# ControlBoard.net
KiCad netlist of a schematic drawn in Altium Designer
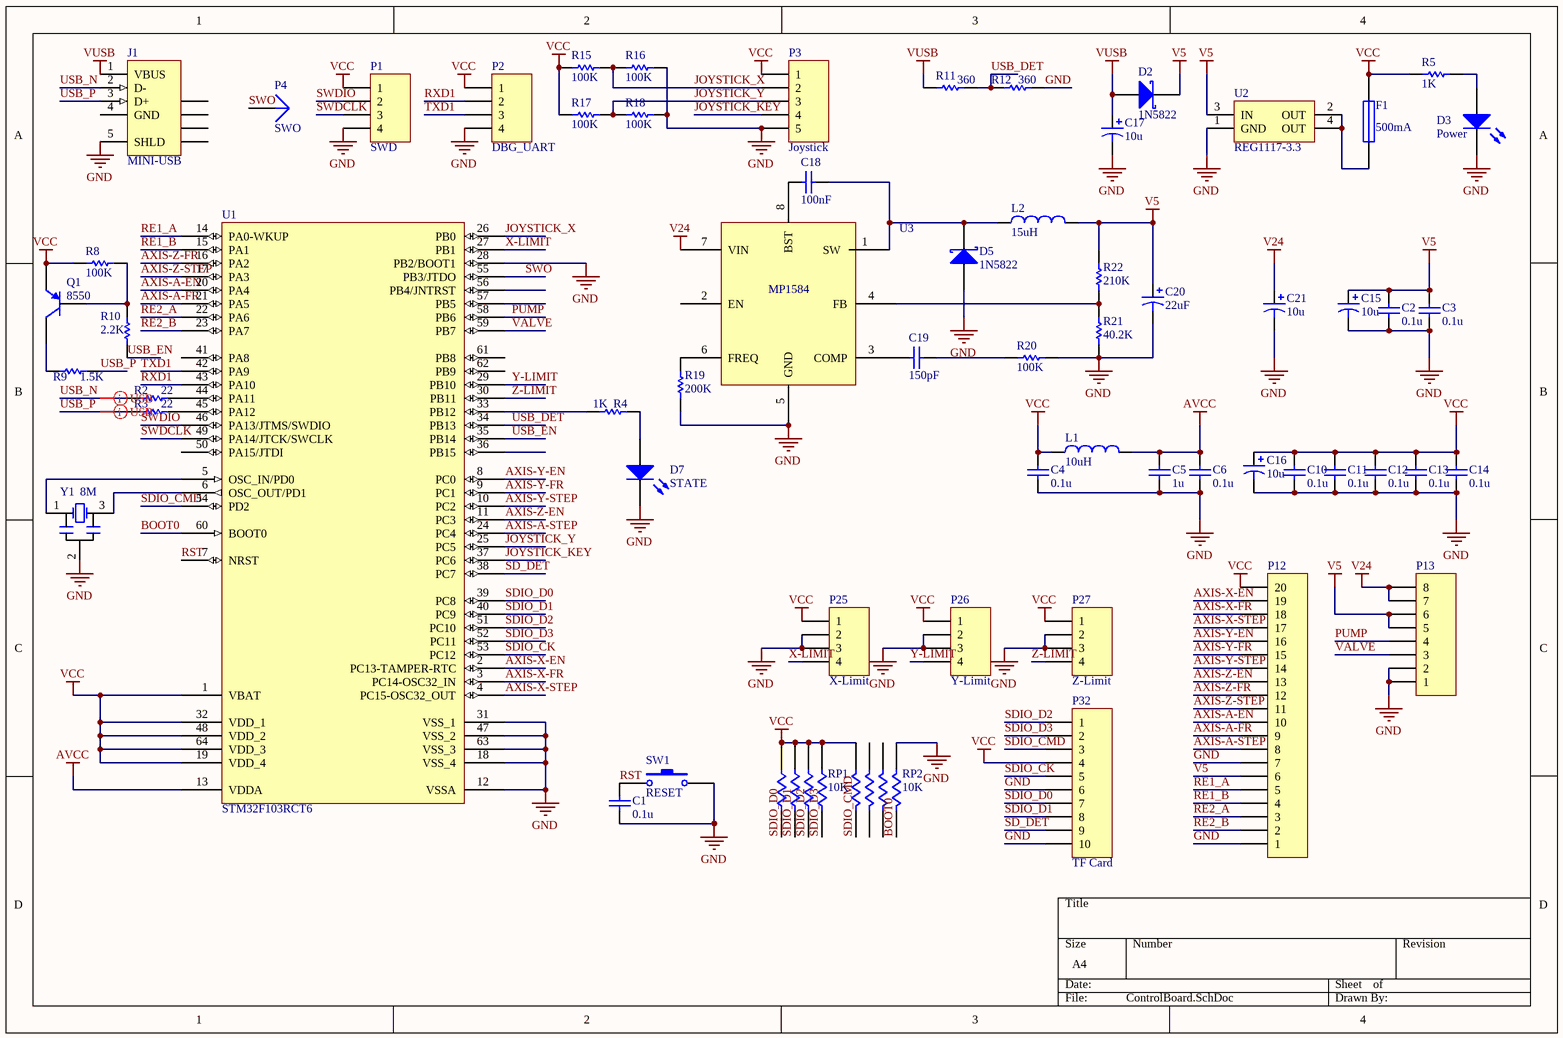
[diagram p0: ControlBoard.SchDoc]

(export (version "E")
  (design (tool "Eeschema 10.0.6"))
  (components
    (comp (ref "C1")
      (value "0.1u")
      (footprint "C-1608[0603]")
      (description "Capacitor (Semiconductor SIM Model)")
      (fields (field (name "Comment") "Cap Semi") (field (name "PUBLISHER") "Altium Limited"))
      (libsource (lib "Miscellaneous Devices") (part "Cap Semi"))
    )
    (comp (ref "C2")
      (value "0.1u")
      (footprint "C-1608[0603]")
      (description "Capacitor (Semiconductor SIM Model)")
      (fields (field (name "Comment") "Cap Semi") (field (name "PUBLISHER") "Altium Limited"))
      (libsource (lib "Miscellaneous Devices") (part "Cap Semi"))
    )
    (comp (ref "C3")
      (value "0.1u")
      (footprint "C-1608[0603]")
      (description "Capacitor (Semiconductor SIM Model)")
      (fields (field (name "Comment") "Cap Semi") (field (name "PUBLISHER") "Altium Limited"))
      (libsource (lib "Miscellaneous Devices") (part "Cap Semi"))
    )
    (comp (ref "C4")
      (value "0.1u")
      (footprint "C-1608[0603]")
      (description "Capacitor (Semiconductor SIM Model)")
      (fields (field (name "Comment") "Cap Semi") (field (name "PUBLISHER") "Altium Limited"))
      (libsource (lib "Miscellaneous Devices") (part "Cap Semi"))
    )
    (comp (ref "C5")
      (value "1u")
      (footprint "C-1608[0603]")
      (description "Capacitor (Semiconductor SIM Model)")
      (fields (field (name "Comment") "Cap Semi") (field (name "PUBLISHER") "Altium Limited"))
      (libsource (lib "Miscellaneous Devices") (part "Cap Semi"))
    )
    (comp (ref "C6")
      (value "0.1u")
      (footprint "C-1608[0603]")
      (description "Capacitor (Semiconductor SIM Model)")
      (fields (field (name "Comment") "Cap Semi") (field (name "PUBLISHER") "Altium Limited"))
      (libsource (lib "Miscellaneous Devices") (part "Cap Semi"))
    )
    (comp (ref "C10")
      (value "0.1u")
      (footprint "C-1608[0603]")
      (description "Capacitor (Semiconductor SIM Model)")
      (fields (field (name "Comment") "Cap Semi") (field (name "PUBLISHER") "Altium Limited"))
      (libsource (lib "Miscellaneous Devices") (part "Cap Semi"))
    )
    (comp (ref "C11")
      (value "0.1u")
      (footprint "C-1608[0603]")
      (description "Capacitor (Semiconductor SIM Model)")
      (fields (field (name "Comment") "Cap Semi") (field (name "PUBLISHER") "Altium Limited"))
      (libsource (lib "Miscellaneous Devices") (part "Cap Semi"))
    )
    (comp (ref "C12")
      (value "0.1u")
      (footprint "C-1608[0603]")
      (description "Capacitor (Semiconductor SIM Model)")
      (fields (field (name "Comment") "Cap Semi") (field (name "PUBLISHER") "Altium Limited"))
      (libsource (lib "Miscellaneous Devices") (part "Cap Semi"))
    )
    (comp (ref "C13")
      (value "0.1u")
      (footprint "C-1608[0603]")
      (description "Capacitor (Semiconductor SIM Model)")
      (fields (field (name "Comment") "Cap Semi") (field (name "PUBLISHER") "Altium Limited"))
      (libsource (lib "Miscellaneous Devices") (part "Cap Semi"))
    )
    (comp (ref "C14")
      (value "0.1u")
      (footprint "C-1608[0603]")
      (description "Capacitor (Semiconductor SIM Model)")
      (fields (field (name "Comment") "Cap Semi") (field (name "PUBLISHER") "Altium Limited"))
      (libsource (lib "Miscellaneous Devices") (part "Cap Semi"))
    )
    (comp (ref "C15")
      (value "10u")
      (footprint "C-2012[0805]")
      (description "Polarized Capacitor (Surface Mount)")
      (fields (field (name "Comment") "Cap Pol3") (field (name "PUBLISHER") "Altium Limited"))
      (libsource (lib "Miscellaneous Devices") (part "Cap Pol3"))
    )
    (comp (ref "C16")
      (value "10u")
      (footprint "C-2012[0805]")
      (description "Polarized Capacitor (Surface Mount)")
      (fields (field (name "Comment") "Cap Pol3") (field (name "PUBLISHER") "Altium Limited"))
      (libsource (lib "Miscellaneous Devices") (part "Cap Pol3"))
    )
    (comp (ref "C17")
      (value "10u")
      (footprint "C-2012[0805]")
      (description "Polarized Capacitor (Surface Mount)")
      (fields (field (name "Comment") "Cap Pol3") (field (name "PUBLISHER") "Altium Limited"))
      (libsource (lib "Miscellaneous Devices") (part "Cap Pol3"))
    )
    (comp (ref "C18")
      (value "100nF")
      (footprint "C-1608[0603]")
      (description "Capacitor (Semiconductor SIM Model)")
      (fields (field (name "Comment") "Cap Semi") (field (name "PUBLISHER") "Altium Limited"))
      (libsource (lib "Miscellaneous Devices") (part "Cap Semi"))
    )
    (comp (ref "C19")
      (value "150pF")
      (footprint "C-1608[0603]")
      (description "Capacitor (Semiconductor SIM Model)")
      (fields (field (name "Comment") "Cap Semi") (field (name "PUBLISHER") "Altium Limited"))
      (libsource (lib "Miscellaneous Devices") (part "Cap Semi"))
    )
    (comp (ref "C20")
      (value "22uF")
      (footprint "C1206")
      (description "Polarized Capacitor (Surface Mount)")
      (fields (field (name "Comment") "Cap Pol3") (field (name "PUBLISHER") "Altium Limited"))
      (libsource (lib "Miscellaneous Devices") (part "Cap Pol3"))
    )
    (comp (ref "C21")
      (value "10u")
      (footprint "C1206")
      (description "Polarized Capacitor (Surface Mount)")
      (fields (field (name "Comment") "Cap Pol3") (field (name "PUBLISHER") "Altium Limited"))
      (libsource (lib "Miscellaneous Devices") (part "Cap Pol3"))
    )
    (comp (ref "D2")
      (value "1N5822")
      (footprint "DO-214AC")
      (description "Schottky Diode")
      (fields (field (name "PUBLISHER") "Altium Limited"))
      (libsource (lib "Miscellaneous Devices") (part "D Schottky"))
    )
    (comp (ref "D3")
      (value "Power")
      (footprint "LED-0805")
      (description "Typical RED, GREEN, YELLOW, AMBER GaAs LED")
      (fields (field (name "PUBLISHER") "Altium Limited"))
      (libsource (lib "Miscellaneous Devices") (part "LED2"))
    )
    (comp (ref "D5")
      (value "1N5822")
      (footprint "DO-214AC")
      (description "Schottky Diode")
      (fields (field (name "PUBLISHER") "Altium Limited"))
      (libsource (lib "Miscellaneous Devices") (part "D Schottky"))
    )
    (comp (ref "D7")
      (value "STATE")
      (footprint "LED-0805")
      (description "Typical RED, GREEN, YELLOW, AMBER GaAs LED")
      (fields (field (name "PUBLISHER") "Altium Limited"))
      (libsource (lib "Miscellaneous Devices") (part "LED2"))
    )
    (comp (ref "F1")
      (value "500mA")
      (footprint "2012[0805]")
      (description "Fuse")
      (fields (field (name "PUBLISHER") "Altium Limited"))
      (libsource (lib "Miscellaneous Devices") (part "Fuse 1"))
    )
    (comp (ref "J1")
      (value "MINI-USB")
      (footprint "Mini USB 3D")
      (description "USB 2.0, Right Angle, SMT, A Type, Receptacle, 5 Position, Black")
      (fields (field (name "PUBLISHER") "Altium Limited"))
      (libsource (lib "AMP Serial Bus USB") (part "440478-1"))
    )
    (comp (ref "L1")
      (value "10uH")
      (footprint "L0603")
      (description "Inductor")
      (fields (field (name "PUBLISHER") "Altium Limited"))
      (libsource (lib "Miscellaneous Devices") (part "Inductor"))
    )
    (comp (ref "L2")
      (value "15uH")
      (footprint "GDRH104R")
      (description "Inductor")
      (fields (field (name "PUBLISHER") "Altium Limited"))
      (libsource (lib "Miscellaneous Devices") (part "Inductor"))
    )
    (comp (ref "P1")
      (value "SWD")
      (footprint "HDR1X4")
      (description "Header, 4-Pin")
      (fields (field (name "PUBLISHER") "Altium Limited"))
      (libsource (lib "Miscellaneous Connectors") (part "Header 4"))
    )
    (comp (ref "P2")
      (value "DBG_UART")
      (footprint "HDR1X4")
      (description "Header, 4-Pin")
      (fields (field (name "PUBLISHER") "Altium Limited"))
      (libsource (lib "Miscellaneous Connectors") (part "Header 4"))
    )
    (comp (ref "P3")
      (value "Joystick")
      (footprint "HDR1X5")
      (description "Header, 5-Pin")
      (fields (field (name "PUBLISHER") "Altium Limited"))
      (libsource (lib "Miscellaneous Connectors") (part "Header 5"))
    )
    (comp (ref "P4")
      (value "SWO")
      (footprint "HDR1X1")
      (description "Plug")
      (fields (field (name "PUBLISHER") "Altium Limited"))
      (libsource (lib "Miscellaneous Connectors") (part "Plug"))
    )
    (comp (ref "P12")
      (value "Header 20")
      (footprint "HDR1X20-3D")
      (description "Header, 20-Pin")
      (fields (field (name "PUBLISHER") "Altium Limited"))
      (libsource (lib "Miscellaneous Connectors") (part "Header 20"))
    )
    (comp (ref "P13")
      (value "Header 8")
      (footprint "HDR1X8-3D")
      (description "Header, 8-Pin")
      (fields (field (name "PUBLISHER") "Altium Limited"))
      (libsource (lib "Miscellaneous Connectors") (part "Header 8"))
    )
    (comp (ref "P25")
      (value "X-Limit")
      (footprint "HDR1X4")
      (description "Header, 4-Pin")
      (fields (field (name "PUBLISHER") "Altium Limited"))
      (libsource (lib "Miscellaneous Connectors") (part "Header 4"))
    )
    (comp (ref "P26")
      (value "Y-Limit")
      (footprint "HDR1X4")
      (description "Header, 4-Pin")
      (fields (field (name "PUBLISHER") "Altium Limited"))
      (libsource (lib "Miscellaneous Connectors") (part "Header 4"))
    )
    (comp (ref "P27")
      (value "Z-Limit")
      (footprint "HDR1X4")
      (description "Header, 4-Pin")
      (fields (field (name "PUBLISHER") "Altium Limited"))
      (libsource (lib "Miscellaneous Connectors") (part "Header 4"))
    )
    (comp (ref "P32")
      (value "TF Card")
      (footprint "MicroSD auto")
      (description "Header, 10-Pin")
      (fields (field (name "PUBLISHER") "Altium Limited"))
      (libsource (lib "Miscellaneous Connectors") (part "Header 10"))
    )
    (comp (ref "Q1")
      (value "8550")
      (footprint "SOT23B")
      (description "PNP Bipolar Transistor")
      (fields (field (name "PUBLISHER") "Altium Limited"))
      (libsource (lib "Miscellaneous Devices") (part "PNP"))
    )
    (comp (ref "R2")
      (value "22")
      (footprint "R-1608[0603]")
      (description "Semiconductor Resistor")
      (fields (field (name "Comment") "Res Semi") (field (name "PUBLISHER") "Altium Limited"))
      (libsource (lib "Miscellaneous Devices") (part "Res Semi"))
    )
    (comp (ref "R3")
      (value "22")
      (footprint "R-1608[0603]")
      (description "Semiconductor Resistor")
      (fields (field (name "Comment") "Res Semi") (field (name "PUBLISHER") "Altium Limited"))
      (libsource (lib "Miscellaneous Devices") (part "Res Semi"))
    )
    (comp (ref "R4")
      (value "1K")
      (footprint "R-1608[0603]")
      (description "Semiconductor Resistor")
      (fields (field (name "Comment") "Res Semi") (field (name "PUBLISHER") "Altium Limited"))
      (libsource (lib "Miscellaneous Devices") (part "Res Semi"))
    )
    (comp (ref "R5")
      (value "1K")
      (footprint "R-1608[0603]")
      (description "Semiconductor Resistor")
      (fields (field (name "Comment") "Res Semi") (field (name "PUBLISHER") "Altium Limited"))
      (libsource (lib "Miscellaneous Devices") (part "Res Semi"))
    )
    (comp (ref "R8")
      (value "100K")
      (footprint "R-1608[0603]")
      (description "Semiconductor Resistor")
      (fields (field (name "Comment") "Res Semi") (field (name "PUBLISHER") "Altium Limited"))
      (libsource (lib "Miscellaneous Devices") (part "Res Semi"))
    )
    (comp (ref "R9")
      (value "1.5K")
      (footprint "R-1608[0603]")
      (description "Semiconductor Resistor")
      (fields (field (name "Comment") "Res Semi") (field (name "PUBLISHER") "Altium Limited"))
      (libsource (lib "Miscellaneous Devices") (part "Res Semi"))
    )
    (comp (ref "R10")
      (value "2.2K")
      (footprint "R-1608[0603]")
      (description "Semiconductor Resistor")
      (fields (field (name "Comment") "Res Semi") (field (name "PUBLISHER") "Altium Limited"))
      (libsource (lib "Miscellaneous Devices") (part "Res Semi"))
    )
    (comp (ref "R11")
      (value "360")
      (footprint "R-1608[0603]")
      (description "Semiconductor Resistor")
      (fields (field (name "Comment") "Res Semi") (field (name "PUBLISHER") "Altium Limited"))
      (libsource (lib "Miscellaneous Devices") (part "Res Semi"))
    )
    (comp (ref "R12")
      (value "360")
      (footprint "R-1608[0603]")
      (description "Semiconductor Resistor")
      (fields (field (name "Comment") "Res Semi") (field (name "PUBLISHER") "Altium Limited"))
      (libsource (lib "Miscellaneous Devices") (part "Res Semi"))
    )
    (comp (ref "R15")
      (value "100K")
      (footprint "R-1608[0603]")
      (description "Semiconductor Resistor")
      (fields (field (name "Comment") "Res Semi") (field (name "PUBLISHER") "Altium Limited"))
      (libsource (lib "Miscellaneous Devices") (part "Res Semi"))
    )
    (comp (ref "R16")
      (value "100K")
      (footprint "R-1608[0603]")
      (description "Semiconductor Resistor")
      (fields (field (name "Comment") "Res Semi") (field (name "PUBLISHER") "Altium Limited"))
      (libsource (lib "Miscellaneous Devices") (part "Res Semi"))
    )
    (comp (ref "R17")
      (value "100K")
      (footprint "R-1608[0603]")
      (description "Semiconductor Resistor")
      (fields (field (name "Comment") "Res Semi") (field (name "PUBLISHER") "Altium Limited"))
      (libsource (lib "Miscellaneous Devices") (part "Res Semi"))
    )
    (comp (ref "R18")
      (value "100K")
      (footprint "R-1608[0603]")
      (description "Semiconductor Resistor")
      (fields (field (name "Comment") "Res Semi") (field (name "PUBLISHER") "Altium Limited"))
      (libsource (lib "Miscellaneous Devices") (part "Res Semi"))
    )
    (comp (ref "R19")
      (value "200K")
      (footprint "R-1608[0603]")
      (description "Semiconductor Resistor")
      (fields (field (name "Comment") "Res Semi") (field (name "PUBLISHER") "Altium Limited"))
      (libsource (lib "Miscellaneous Devices") (part "Res Semi"))
    )
    (comp (ref "R20")
      (value "100K")
      (footprint "R-1608[0603]")
      (description "Semiconductor Resistor")
      (fields (field (name "Comment") "Res Semi") (field (name "PUBLISHER") "Altium Limited"))
      (libsource (lib "Miscellaneous Devices") (part "Res Semi"))
    )
    (comp (ref "R21")
      (value "40.2K")
      (footprint "R-1608[0603]")
      (description "Semiconductor Resistor")
      (fields (field (name "Comment") "Res Semi") (field (name "PUBLISHER") "Altium Limited"))
      (libsource (lib "Miscellaneous Devices") (part "Res Semi"))
    )
    (comp (ref "R22")
      (value "210K")
      (footprint "R-1608[0603]")
      (description "Semiconductor Resistor")
      (fields (field (name "Comment") "Res Semi") (field (name "PUBLISHER") "Altium Limited"))
      (libsource (lib "Miscellaneous Devices") (part "Res Semi"))
    )
    (comp (ref "RP1") (value "10K") (footprint "R0603x4") (libsource (lib "Schlib1") (part "RPACK4")))
    (comp (ref "RP2") (value "10K") (footprint "R0603x4") (libsource (lib "Schlib1") (part "RPACK4")))
    (comp (ref "SW1")
      (value "RESET")
      (footprint "SW-3D")
      (description "Switch")
      (fields (field (name "PUBLISHER") "Altium Limited"))
      (libsource (lib "Miscellaneous Devices") (part "SW-PB"))
    )
    (comp (ref "U1")
      (value "STM32F103RCT6")
      (footprint "LQFP64_N")
      (description "STM32 ARM-based 32-bit MCU High-density")
      (fields (field (name "PUBLISHER") "Altium Limited"))
      (libsource (lib "ST Microcontroller 32-Bit STM32") (part "STM32F103RBT6"))
    )
    (comp (ref "U2")
      (value "REG1117-3.3")
      (footprint "SOT223-3D")
      (description "800mA and 1A Low Dropout Positive Regulator 2.85V, 3.3V, 5V, and Adjustable")
      (fields (field (name "PUBLISHER") "Altium Limited"))
      (libsource (lib "BB Power Mgt Voltage Regulator") (part "REG1117-3.3"))
    )
    (comp (ref "U3") (value "MP1584") (footprint "MP1584") (libsource (lib "Schlib1") (part "MP1584")))
    (comp (ref "Y1")
      (value "8M")
      (footprint "Crystal_C")
      (description "Crystal Oscillator")
      (fields (field (name "PUBLISHER") "Altium Limited"))
      (libsource (lib "Schlib1") (part "XTAL_C"))
    )
  )
  (nets
    (net (code "1") (name "/AXIS-A-EN") (class "Default")
      (node (ref "P12") (pin "10") (pinfunction "10_10") (pintype "passive"))
      (node (ref "U1") (pin "20") (pinfunction "PA4_20") (pintype "bidirectional"))
    )
    (net (code "2") (name "/AXIS-A-FR") (class "Default")
      (node (ref "P12") (pin "9") (pinfunction "9_9") (pintype "passive"))
      (node (ref "U1") (pin "21") (pinfunction "PA5_21") (pintype "bidirectional"))
    )
    (net (code "3") (name "/AXIS-A-STEP") (class "Default")
      (node (ref "P12") (pin "8") (pinfunction "8_8") (pintype "passive"))
      (node (ref "U1") (pin "24") (pinfunction "PC4_24") (pintype "bidirectional"))
    )
    (net (code "4") (name "/AXIS-X-EN") (class "Default")
      (node (ref "P12") (pin "19") (pinfunction "19_19") (pintype "passive"))
      (node (ref "U1") (pin "2") (pinfunction "PC13-TAMPER-RTC_2") (pintype "bidirectional"))
    )
    (net (code "5") (name "/AXIS-X-FR") (class "Default")
      (node (ref "P12") (pin "18") (pinfunction "18_18") (pintype "passive"))
      (node (ref "U1") (pin "3") (pinfunction "PC14-OSC32_IN_3") (pintype "bidirectional"))
    )
    (net (code "6") (name "/AXIS-X-STEP") (class "Default")
      (node (ref "P12") (pin "17") (pinfunction "17_17") (pintype "passive"))
      (node (ref "U1") (pin "4") (pinfunction "PC15-OSC32_OUT_4") (pintype "bidirectional"))
    )
    (net (code "7") (name "/AXIS-Y-EN") (class "Default")
      (node (ref "P12") (pin "16") (pinfunction "16_16") (pintype "passive"))
      (node (ref "U1") (pin "8") (pinfunction "PC0_8") (pintype "bidirectional"))
    )
    (net (code "8") (name "/AXIS-Y-FR") (class "Default")
      (node (ref "P12") (pin "15") (pinfunction "15_15") (pintype "passive"))
      (node (ref "U1") (pin "9") (pinfunction "PC1_9") (pintype "bidirectional"))
    )
    (net (code "9") (name "/AXIS-Y-STEP") (class "Default")
      (node (ref "P12") (pin "14") (pinfunction "14_14") (pintype "passive"))
      (node (ref "U1") (pin "10") (pinfunction "PC2_10") (pintype "bidirectional"))
    )
    (net (code "10") (name "/AXIS-Z-EN") (class "Default")
      (node (ref "P12") (pin "13") (pinfunction "13_13") (pintype "passive"))
      (node (ref "U1") (pin "11") (pinfunction "PC3_11") (pintype "bidirectional"))
    )
    (net (code "11") (name "/AXIS-Z-FR") (class "Default")
      (node (ref "P12") (pin "12") (pinfunction "12_12") (pintype "passive"))
      (node (ref "U1") (pin "16") (pinfunction "PA2_16") (pintype "bidirectional"))
    )
    (net (code "12") (name "/AXIS-Z-STEP") (class "Default")
      (node (ref "P12") (pin "11") (pinfunction "11_11") (pintype "passive"))
      (node (ref "U1") (pin "17") (pinfunction "PA3_17") (pintype "bidirectional"))
    )
    (net (code "13") (name "/BOOT0") (class "Default")
      (node (ref "RP2") (pin "5") (pinfunction "5_5") (pintype "passive"))
      (node (ref "U1") (pin "60") (pinfunction "BOOT0_60") (pintype "input"))
    )
    (net (code "14") (name "/JOYSTICK_KEY") (class "Default")
      (node (ref "P3") (pin "4") (pinfunction "4_4") (pintype "passive"))
      (node (ref "U1") (pin "37") (pinfunction "PC6_37") (pintype "bidirectional"))
    )
    (net (code "15") (name "/JOYSTICK_X") (class "Default")
      (node (ref "P3") (pin "2") (pinfunction "2_2") (pintype "passive"))
      (node (ref "R15") (pin "1") (pinfunction "1_1") (pintype "passive"))
      (node (ref "R16") (pin "2") (pinfunction "2_2") (pintype "passive"))
      (node (ref "U1") (pin "26") (pinfunction "PB0_26") (pintype "bidirectional"))
    )
    (net (code "16") (name "/JOYSTICK_Y") (class "Default")
      (node (ref "P3") (pin "3") (pinfunction "3_3") (pintype "passive"))
      (node (ref "R17") (pin "1") (pinfunction "1_1") (pintype "passive"))
      (node (ref "R18") (pin "2") (pinfunction "2_2") (pintype "passive"))
      (node (ref "U1") (pin "25") (pinfunction "PC5_25") (pintype "bidirectional"))
    )
    (net (code "17") (name "/PUMP") (class "Default")
      (node (ref "P13") (pin "4") (pinfunction "4_4") (pintype "passive"))
      (node (ref "U1") (pin "58") (pinfunction "PB6_58") (pintype "bidirectional"))
    )
    (net (code "18") (name "/RE1_A") (class "Default")
      (node (ref "P12") (pin "5") (pinfunction "5_5") (pintype "passive"))
      (node (ref "U1") (pin "14") (pinfunction "PA0-WKUP_14") (pintype "bidirectional"))
    )
    (net (code "19") (name "/RE1_B") (class "Default")
      (node (ref "P12") (pin "4") (pinfunction "4_4") (pintype "passive"))
      (node (ref "U1") (pin "15") (pinfunction "PA1_15") (pintype "bidirectional"))
    )
    (net (code "20") (name "/RE2_A") (class "Default")
      (node (ref "P12") (pin "3") (pinfunction "3_3") (pintype "passive"))
      (node (ref "U1") (pin "22") (pinfunction "PA6_22") (pintype "bidirectional"))
    )
    (net (code "21") (name "/RE2_B") (class "Default")
      (node (ref "P12") (pin "2") (pinfunction "2_2") (pintype "passive"))
      (node (ref "U1") (pin "23") (pinfunction "PA7_23") (pintype "bidirectional"))
    )
    (net (code "22") (name "/RST") (class "Default")
      (node (ref "C1") (pin "2") (pinfunction "2_2") (pintype "passive"))
      (node (ref "SW1") (pin "1") (pinfunction "1_1") (pintype "passive"))
      (node (ref "U1") (pin "7") (pinfunction "NRST_7") (pintype "bidirectional"))
    )
    (net (code "23") (name "/RXD1") (class "Default")
      (node (ref "P2") (pin "2") (pinfunction "2_2") (pintype "passive"))
      (node (ref "U1") (pin "43") (pinfunction "PA10_43") (pintype "bidirectional"))
    )
    (net (code "24") (name "/SDIO_CK") (class "Default")
      (node (ref "P32") (pin "5") (pinfunction "5_5") (pintype "passive"))
      (node (ref "U1") (pin "53") (pinfunction "PC12_53") (pintype "bidirectional"))
    )
    (net (code "25") (name "/SDIO_CMD") (class "Default")
      (node (ref "P32") (pin "3") (pinfunction "3_3") (pintype "passive"))
      (node (ref "RP2") (pin "8") (pinfunction "8_8") (pintype "passive"))
      (node (ref "U1") (pin "54") (pinfunction "PD2_54") (pintype "bidirectional"))
    )
    (net (code "26") (name "/SDIO_D0") (class "Default")
      (node (ref "P32") (pin "7") (pinfunction "7_7") (pintype "passive"))
      (node (ref "RP1") (pin "1") (pinfunction "1_1") (pintype "passive"))
      (node (ref "U1") (pin "39") (pinfunction "PC8_39") (pintype "bidirectional"))
    )
    (net (code "27") (name "/SDIO_D1") (class "Default")
      (node (ref "P32") (pin "8") (pinfunction "8_8") (pintype "passive"))
      (node (ref "RP1") (pin "2") (pinfunction "2_2") (pintype "passive"))
      (node (ref "U1") (pin "40") (pinfunction "PC9_40") (pintype "bidirectional"))
    )
    (net (code "28") (name "/SDIO_D2") (class "Default")
      (node (ref "P32") (pin "1") (pinfunction "1_1") (pintype "passive"))
      (node (ref "RP1") (pin "3") (pinfunction "3_3") (pintype "passive"))
      (node (ref "U1") (pin "51") (pinfunction "PC10_51") (pintype "bidirectional"))
    )
    (net (code "29") (name "/SDIO_D3") (class "Default")
      (node (ref "P32") (pin "2") (pinfunction "2_2") (pintype "passive"))
      (node (ref "RP1") (pin "4") (pinfunction "4_4") (pintype "passive"))
      (node (ref "U1") (pin "52") (pinfunction "PC11_52") (pintype "bidirectional"))
    )
    (net (code "30") (name "/SD_DET") (class "Default")
      (node (ref "P32") (pin "9") (pinfunction "9_9") (pintype "passive"))
      (node (ref "U1") (pin "38") (pinfunction "PC7_38") (pintype "bidirectional"))
    )
    (net (code "31") (name "/SWDCLK") (class "Default")
      (node (ref "P1") (pin "3") (pinfunction "3_3") (pintype "passive"))
      (node (ref "U1") (pin "49") (pinfunction "PA14/JTCK/SWCLK_49") (pintype "bidirectional"))
    )
    (net (code "32") (name "/SWDIO") (class "Default")
      (node (ref "P1") (pin "2") (pinfunction "2_2") (pintype "passive"))
      (node (ref "U1") (pin "46") (pinfunction "PA13/JTMS/SWDIO_46") (pintype "bidirectional"))
    )
    (net (code "33") (name "/SWO") (class "Default")
      (node (ref "P4") (pin "1") (pinfunction "1_1") (pintype "passive"))
      (node (ref "U1") (pin "55") (pinfunction "PB3/JTDO_55") (pintype "bidirectional"))
    )
    (net (code "34") (name "/TXD1") (class "Default")
      (node (ref "P2") (pin "3") (pinfunction "3_3") (pintype "passive"))
      (node (ref "U1") (pin "42") (pinfunction "PA9_42") (pintype "bidirectional"))
    )
    (net (code "35") (name "/USB_DET") (class "Default")
      (node (ref "R11") (pin "1") (pinfunction "1_1") (pintype "passive"))
      (node (ref "R12") (pin "2") (pinfunction "2_2") (pintype "passive"))
      (node (ref "U1") (pin "34") (pinfunction "PB13_34") (pintype "bidirectional"))
    )
    (net (code "36") (name "/USB_EN") (class "Default")
      (node (ref "R10") (pin "1") (pinfunction "1_1") (pintype "passive"))
      (node (ref "U1") (pin "35") (pinfunction "PB14_35") (pintype "bidirectional"))
    )
    (net (code "37") (name "/USB_N") (class "Default")
      (node (ref "J1") (pin "2") (pinfunction "D-_2") (pintype "input"))
      (node (ref "R2") (pin "1") (pinfunction "1_1") (pintype "passive"))
    )
    (net (code "38") (name "/USB_P") (class "Default")
      (node (ref "J1") (pin "3") (pinfunction "D+_3") (pintype "input"))
      (node (ref "R3") (pin "1") (pinfunction "1_1") (pintype "passive"))
      (node (ref "R9") (pin "1") (pinfunction "1_1") (pintype "passive"))
    )
    (net (code "39") (name "/VALVE") (class "Default")
      (node (ref "P13") (pin "3") (pinfunction "3_3") (pintype "passive"))
      (node (ref "U1") (pin "59") (pinfunction "PB7_59") (pintype "bidirectional"))
    )
    (net (code "40") (name "/X-LIMIT") (class "Default")
      (node (ref "P25") (pin "4") (pinfunction "4_4") (pintype "passive"))
      (node (ref "U1") (pin "27") (pinfunction "PB1_27") (pintype "bidirectional"))
    )
    (net (code "41") (name "/Y-LIMIT") (class "Default")
      (node (ref "P26") (pin "4") (pinfunction "4_4") (pintype "passive"))
      (node (ref "U1") (pin "29") (pinfunction "PB10_29") (pintype "bidirectional"))
    )
    (net (code "42") (name "/Z-LIMIT") (class "Default")
      (node (ref "P27") (pin "4") (pinfunction "4_4") (pintype "passive"))
      (node (ref "U1") (pin "30") (pinfunction "PB11_30") (pintype "bidirectional"))
    )
    (net (code "43") (name "AVCC") (class "Default")
      (node (ref "C5") (pin "2") (pinfunction "2_2") (pintype "passive"))
      (node (ref "C6") (pin "2") (pinfunction "2_2") (pintype "passive"))
      (node (ref "L1") (pin "2") (pinfunction "2_2") (pintype "passive"))
      (node (ref "U1") (pin "13") (pinfunction "VDDA_13") (pintype "power_in"))
    )
    (net (code "44") (name "GND") (class "Default")
      (node (ref "C1") (pin "1") (pinfunction "1_1") (pintype "passive"))
      (node (ref "C10") (pin "1") (pinfunction "1_1") (pintype "passive"))
      (node (ref "C11") (pin "1") (pinfunction "1_1") (pintype "passive"))
      (node (ref "C12") (pin "1") (pinfunction "1_1") (pintype "passive"))
      (node (ref "C13") (pin "1") (pinfunction "1_1") (pintype "passive"))
      (node (ref "C14") (pin "1") (pinfunction "1_1") (pintype "passive"))
      (node (ref "C15") (pin "2") (pinfunction "2_2") (pintype "passive"))
      (node (ref "C16") (pin "2") (pinfunction "2_2") (pintype "passive"))
      (node (ref "C17") (pin "2") (pinfunction "2_2") (pintype "passive"))
      (node (ref "C2") (pin "1") (pinfunction "1_1") (pintype "passive"))
      (node (ref "C20") (pin "2") (pinfunction "2_2") (pintype "passive"))
      (node (ref "C21") (pin "2") (pinfunction "2_2") (pintype "passive"))
      (node (ref "C3") (pin "1") (pinfunction "1_1") (pintype "passive"))
      (node (ref "C4") (pin "1") (pinfunction "1_1") (pintype "passive"))
      (node (ref "C5") (pin "1") (pinfunction "1_1") (pintype "passive"))
      (node (ref "C6") (pin "1") (pinfunction "1_1") (pintype "passive"))
      (node (ref "D3") (pin "2") (pinfunction "K_2") (pintype "passive"))
      (node (ref "D5") (pin "1") (pinfunction "A_1") (pintype "passive"))
      (node (ref "D7") (pin "2") (pinfunction "K_2") (pintype "passive"))
      (node (ref "J1") (pin "5") (pinfunction "SHLD_5") (pintype "passive"))
      (node (ref "P1") (pin "4") (pinfunction "4_4") (pintype "passive"))
      (node (ref "P12") (pin "1") (pinfunction "1_1") (pintype "passive"))
      (node (ref "P12") (pin "7") (pinfunction "7_7") (pintype "passive"))
      (node (ref "P13") (pin "1") (pinfunction "1_1") (pintype "passive"))
      (node (ref "P13") (pin "2") (pinfunction "2_2") (pintype "passive"))
      (node (ref "P2") (pin "4") (pinfunction "4_4") (pintype "passive"))
      (node (ref "P25") (pin "2") (pinfunction "2_2") (pintype "passive"))
      (node (ref "P25") (pin "3") (pinfunction "3_3") (pintype "passive"))
      (node (ref "P26") (pin "2") (pinfunction "2_2") (pintype "passive"))
      (node (ref "P26") (pin "3") (pinfunction "3_3") (pintype "passive"))
      (node (ref "P27") (pin "2") (pinfunction "2_2") (pintype "passive"))
      (node (ref "P27") (pin "3") (pinfunction "3_3") (pintype "passive"))
      (node (ref "P3") (pin "5") (pinfunction "5_5") (pintype "passive"))
      (node (ref "P32") (pin "10") (pinfunction "10_10") (pintype "passive"))
      (node (ref "P32") (pin "6") (pinfunction "6_6") (pintype "passive"))
      (node (ref "R12") (pin "1") (pinfunction "1_1") (pintype "passive"))
      (node (ref "R16") (pin "1") (pinfunction "1_1") (pintype "passive"))
      (node (ref "R18") (pin "1") (pinfunction "1_1") (pintype "passive"))
      (node (ref "R19") (pin "1") (pinfunction "1_1") (pintype "passive"))
      (node (ref "R20") (pin "1") (pinfunction "1_1") (pintype "passive"))
      (node (ref "R21") (pin "2") (pinfunction "2_2") (pintype "passive"))
      (node (ref "RP2") (pin "4") (pinfunction "4_4") (pintype "passive"))
      (node (ref "SW1") (pin "2") (pinfunction "2_2") (pintype "passive"))
      (node (ref "U1") (pin "12") (pinfunction "VSSA_12") (pintype "power_in"))
      (node (ref "U1") (pin "18") (pinfunction "VSS_4_18") (pintype "power_in"))
      (node (ref "U1") (pin "28") (pinfunction "PB2/BOOT1_28") (pintype "bidirectional"))
      (node (ref "U1") (pin "31") (pinfunction "VSS_1_31") (pintype "power_in"))
      (node (ref "U1") (pin "47") (pinfunction "VSS_2_47") (pintype "power_in"))
      (node (ref "U1") (pin "63") (pinfunction "VSS_3_63") (pintype "power_in"))
      (node (ref "U2") (pin "1") (pinfunction "GND_1") (pintype "power_in"))
      (node (ref "U3") (pin "5") (pinfunction "GND_5") (pintype "passive"))
      (node (ref "Y1") (pin "2") (pinfunction "GND_2") (pintype "passive"))
    )
    (net (code "45") (name "Net-(C19-Pad1)") (class "Default")
      (node (ref "C19") (pin "1") (pinfunction "1_1") (pintype "passive"))
      (node (ref "R20") (pin "2") (pinfunction "2_2") (pintype "passive"))
    )
    (net (code "46") (name "Net-(D3-A)") (class "Default")
      (node (ref "D3") (pin "1") (pinfunction "A_1") (pintype "passive"))
      (node (ref "R5") (pin "1") (pinfunction "1_1") (pintype "passive"))
    )
    (net (code "47") (name "Net-(D5-K)") (class "Default")
      (node (ref "C18") (pin "1") (pinfunction "1_1") (pintype "passive"))
      (node (ref "D5") (pin "2") (pinfunction "K_2") (pintype "passive"))
      (node (ref "L2") (pin "1") (pinfunction "1_1") (pintype "passive"))
      (node (ref "U3") (pin "1") (pinfunction "SW_1") (pintype "passive"))
    )
    (net (code "48") (name "Net-(D7-A)") (class "Default")
      (node (ref "D7") (pin "1") (pinfunction "A_1") (pintype "passive"))
      (node (ref "R4") (pin "2") (pinfunction "2_2") (pintype "passive"))
    )
    (net (code "49") (name "Net-(F1-Pad1)") (class "Default")
      (node (ref "F1") (pin "1") (pinfunction "1_1") (pintype "passive"))
      (node (ref "U2") (pin "2") (pinfunction "OUT_2") (pintype "power_in"))
      (node (ref "U2") (pin "4") (pinfunction "OUT_4") (pintype "power_in"))
    )
    (net (code "50") (name "Net-(Q1-B)") (class "Default")
      (node (ref "Q1") (pin "2") (pinfunction "B_2") (pintype "passive"))
      (node (ref "R10") (pin "2") (pinfunction "2_2") (pintype "passive"))
      (node (ref "R8") (pin "1") (pinfunction "1_1") (pintype "passive"))
    )
    (net (code "51") (name "Net-(Q1-C)") (class "Default")
      (node (ref "Q1") (pin "1") (pinfunction "C_1") (pintype "passive"))
      (node (ref "R9") (pin "2") (pinfunction "2_2") (pintype "passive"))
    )
    (net (code "52") (name "Net-(U1-OSC_IN{slash}PD0)") (class "Default")
      (node (ref "U1") (pin "5") (pinfunction "OSC_IN/PD0_5") (pintype "input"))
      (node (ref "Y1") (pin "1") (pinfunction "OSC1_1") (pintype "passive"))
    )
    (net (code "53") (name "Net-(U1-OSC_OUT{slash}PD1)") (class "Default")
      (node (ref "U1") (pin "6") (pinfunction "OSC_OUT/PD1_6") (pintype "output"))
      (node (ref "Y1") (pin "3") (pinfunction "OSC2_3") (pintype "passive"))
    )
    (net (code "54") (name "Net-(U1-PA11)") (class "Default")
      (node (ref "R2") (pin "2") (pinfunction "2_2") (pintype "passive"))
      (node (ref "U1") (pin "44") (pinfunction "PA11_44") (pintype "bidirectional"))
    )
    (net (code "55") (name "Net-(U1-PA12)") (class "Default")
      (node (ref "R3") (pin "2") (pinfunction "2_2") (pintype "passive"))
      (node (ref "U1") (pin "45") (pinfunction "PA12_45") (pintype "bidirectional"))
    )
    (net (code "56") (name "Net-(U1-PB12)") (class "Default")
      (node (ref "R4") (pin "1") (pinfunction "1_1") (pintype "passive"))
      (node (ref "U1") (pin "33") (pinfunction "PB12_33") (pintype "bidirectional"))
    )
    (net (code "57") (name "Net-(U3-BST)") (class "Default")
      (node (ref "C18") (pin "2") (pinfunction "2_2") (pintype "passive"))
      (node (ref "U3") (pin "8") (pinfunction "BST_8") (pintype "passive"))
    )
    (net (code "58") (name "Net-(U3-COMP)") (class "Default")
      (node (ref "C19") (pin "2") (pinfunction "2_2") (pintype "passive"))
      (node (ref "U3") (pin "3") (pinfunction "COMP_3") (pintype "passive"))
    )
    (net (code "59") (name "Net-(U3-FB)") (class "Default")
      (node (ref "R21") (pin "1") (pinfunction "1_1") (pintype "passive"))
      (node (ref "R22") (pin "2") (pinfunction "2_2") (pintype "passive"))
      (node (ref "U3") (pin "4") (pinfunction "FB_4") (pintype "passive"))
    )
    (net (code "60") (name "Net-(U3-FREQ)") (class "Default")
      (node (ref "R19") (pin "2") (pinfunction "2_2") (pintype "passive"))
      (node (ref "U3") (pin "6") (pinfunction "FREQ_6") (pintype "passive"))
    )
    (net (code "61") (name "V5") (class "Default")
      (node (ref "C15") (pin "1") (pinfunction "1_1") (pintype "passive"))
      (node (ref "C2") (pin "2") (pinfunction "2_2") (pintype "passive"))
      (node (ref "C20") (pin "1") (pinfunction "1_1") (pintype "passive"))
      (node (ref "C3") (pin "2") (pinfunction "2_2") (pintype "passive"))
      (node (ref "D2") (pin "2") (pinfunction "K_2") (pintype "passive"))
      (node (ref "L2") (pin "2") (pinfunction "2_2") (pintype "passive"))
      (node (ref "P12") (pin "6") (pinfunction "6_6") (pintype "passive"))
      (node (ref "P13") (pin "5") (pinfunction "5_5") (pintype "passive"))
      (node (ref "P13") (pin "6") (pinfunction "6_6") (pintype "passive"))
      (node (ref "R22") (pin "1") (pinfunction "1_1") (pintype "passive"))
      (node (ref "U2") (pin "3") (pinfunction "IN_3") (pintype "power_in"))
    )
    (net (code "62") (name "V24") (class "Default")
      (node (ref "C21") (pin "1") (pinfunction "1_1") (pintype "passive"))
      (node (ref "P13") (pin "7") (pinfunction "7_7") (pintype "passive"))
      (node (ref "P13") (pin "8") (pinfunction "8_8") (pintype "passive"))
      (node (ref "U3") (pin "7") (pinfunction "VIN_7") (pintype "passive"))
    )
    (net (code "63") (name "VCC") (class "Default")
      (node (ref "C10") (pin "2") (pinfunction "2_2") (pintype "passive"))
      (node (ref "C11") (pin "2") (pinfunction "2_2") (pintype "passive"))
      (node (ref "C12") (pin "2") (pinfunction "2_2") (pintype "passive"))
      (node (ref "C13") (pin "2") (pinfunction "2_2") (pintype "passive"))
      (node (ref "C14") (pin "2") (pinfunction "2_2") (pintype "passive"))
      (node (ref "C16") (pin "1") (pinfunction "1_1") (pintype "passive"))
      (node (ref "C4") (pin "2") (pinfunction "2_2") (pintype "passive"))
      (node (ref "F1") (pin "2") (pinfunction "2_2") (pintype "passive"))
      (node (ref "L1") (pin "1") (pinfunction "1_1") (pintype "passive"))
      (node (ref "P1") (pin "1") (pinfunction "1_1") (pintype "passive"))
      (node (ref "P12") (pin "20") (pinfunction "20_20") (pintype "passive"))
      (node (ref "P2") (pin "1") (pinfunction "1_1") (pintype "passive"))
      (node (ref "P25") (pin "1") (pinfunction "1_1") (pintype "passive"))
      (node (ref "P26") (pin "1") (pinfunction "1_1") (pintype "passive"))
      (node (ref "P27") (pin "1") (pinfunction "1_1") (pintype "passive"))
      (node (ref "P3") (pin "1") (pinfunction "1_1") (pintype "passive"))
      (node (ref "P32") (pin "4") (pinfunction "4_4") (pintype "passive"))
      (node (ref "Q1") (pin "3") (pinfunction "E_3") (pintype "passive"))
      (node (ref "R15") (pin "2") (pinfunction "2_2") (pintype "passive"))
      (node (ref "R17") (pin "2") (pinfunction "2_2") (pintype "passive"))
      (node (ref "R5") (pin "2") (pinfunction "2_2") (pintype "passive"))
      (node (ref "R8") (pin "2") (pinfunction "2_2") (pintype "passive"))
      (node (ref "RP1") (pin "5") (pinfunction "5_5") (pintype "passive"))
      (node (ref "RP1") (pin "6") (pinfunction "6_6") (pintype "passive"))
      (node (ref "RP1") (pin "7") (pinfunction "7_7") (pintype "passive"))
      (node (ref "RP1") (pin "8") (pinfunction "8_8") (pintype "passive"))
      (node (ref "RP2") (pin "1") (pinfunction "1_1") (pintype "passive"))
      (node (ref "U1") (pin "1") (pinfunction "VBAT_1") (pintype "power_in"))
      (node (ref "U1") (pin "19") (pinfunction "VDD_4_19") (pintype "power_in"))
      (node (ref "U1") (pin "32") (pinfunction "VDD_1_32") (pintype "power_in"))
      (node (ref "U1") (pin "48") (pinfunction "VDD_2_48") (pintype "power_in"))
      (node (ref "U1") (pin "64") (pinfunction "VDD_3_64") (pintype "power_in"))
    )
    (net (code "64") (name "VUSB") (class "Default")
      (node (ref "C17") (pin "1") (pinfunction "1_1") (pintype "passive"))
      (node (ref "D2") (pin "1") (pinfunction "A_1") (pintype "passive"))
      (node (ref "J1") (pin "1") (pinfunction "VBUS_1") (pintype "power_in"))
      (node (ref "R11") (pin "2") (pinfunction "2_2") (pintype "passive"))
    )
    (net (code "65") (name "unconnected-(J1-GND-Pad4)") (class "Default")
      (node (ref "J1") (pin "4") (pinfunction "GND_4") (pintype "power_in"))
    )
    (net (code "66") (name "unconnected-(J1-SHLD-Pad6)") (class "Default")
      (node (ref "J1") (pin "6") (pinfunction "SHLD_6") (pintype "passive"))
    )
    (net (code "67") (name "unconnected-(J1-SHLD-Pad7)") (class "Default")
      (node (ref "J1") (pin "7") (pinfunction "SHLD_7") (pintype "passive"))
    )
    (net (code "68") (name "unconnected-(J1-SHLD-Pad8)") (class "Default")
      (node (ref "J1") (pin "8") (pinfunction "SHLD_8") (pintype "passive"))
    )
    (net (code "69") (name "unconnected-(J1-SHLD-Pad9)") (class "Default")
      (node (ref "J1") (pin "9") (pinfunction "SHLD_9") (pintype "passive"))
    )
    (net (code "70") (name "unconnected-(RP2-Pad2)") (class "Default")
      (node (ref "RP2") (pin "2") (pinfunction "2_2") (pintype "passive"))
    )
    (net (code "71") (name "unconnected-(RP2-Pad3)") (class "Default")
      (node (ref "RP2") (pin "3") (pinfunction "3_3") (pintype "passive"))
    )
    (net (code "72") (name "unconnected-(RP2-Pad6)") (class "Default")
      (node (ref "RP2") (pin "6") (pinfunction "6_6") (pintype "passive"))
    )
    (net (code "73") (name "unconnected-(RP2-Pad7)") (class "Default")
      (node (ref "RP2") (pin "7") (pinfunction "7_7") (pintype "passive"))
    )
    (net (code "74") (name "unconnected-(U1-PA8-Pad41)") (class "Default")
      (node (ref "U1") (pin "41") (pinfunction "PA8_41") (pintype "bidirectional"))
    )
    (net (code "75") (name "unconnected-(U1-PA15{slash}JTDI-Pad50)") (class "Default")
      (node (ref "U1") (pin "50") (pinfunction "PA15/JTDI_50") (pintype "bidirectional"))
    )
    (net (code "76") (name "unconnected-(U1-PB4{slash}JNTRST-Pad56)") (class "Default")
      (node (ref "U1") (pin "56") (pinfunction "PB4/JNTRST_56") (pintype "bidirectional"))
    )
    (net (code "77") (name "unconnected-(U1-PB5-Pad57)") (class "Default")
      (node (ref "U1") (pin "57") (pinfunction "PB5_57") (pintype "bidirectional"))
    )
    (net (code "78") (name "unconnected-(U1-PB8-Pad61)") (class "Default")
      (node (ref "U1") (pin "61") (pinfunction "PB8_61") (pintype "bidirectional"))
    )
    (net (code "79") (name "unconnected-(U1-PB9-Pad62)") (class "Default")
      (node (ref "U1") (pin "62") (pinfunction "PB9_62") (pintype "bidirectional"))
    )
    (net (code "80") (name "unconnected-(U1-PB15-Pad36)") (class "Default")
      (node (ref "U1") (pin "36") (pinfunction "PB15_36") (pintype "bidirectional"))
    )
    (net (code "81") (name "unconnected-(U3-EN-Pad2)") (class "Default")
      (node (ref "U3") (pin "2") (pinfunction "EN_2") (pintype "passive"))
    )
  )
)
